# 12V--5V--3_3V.net
KiCad netlist of a schematic drawn in Altium Designer
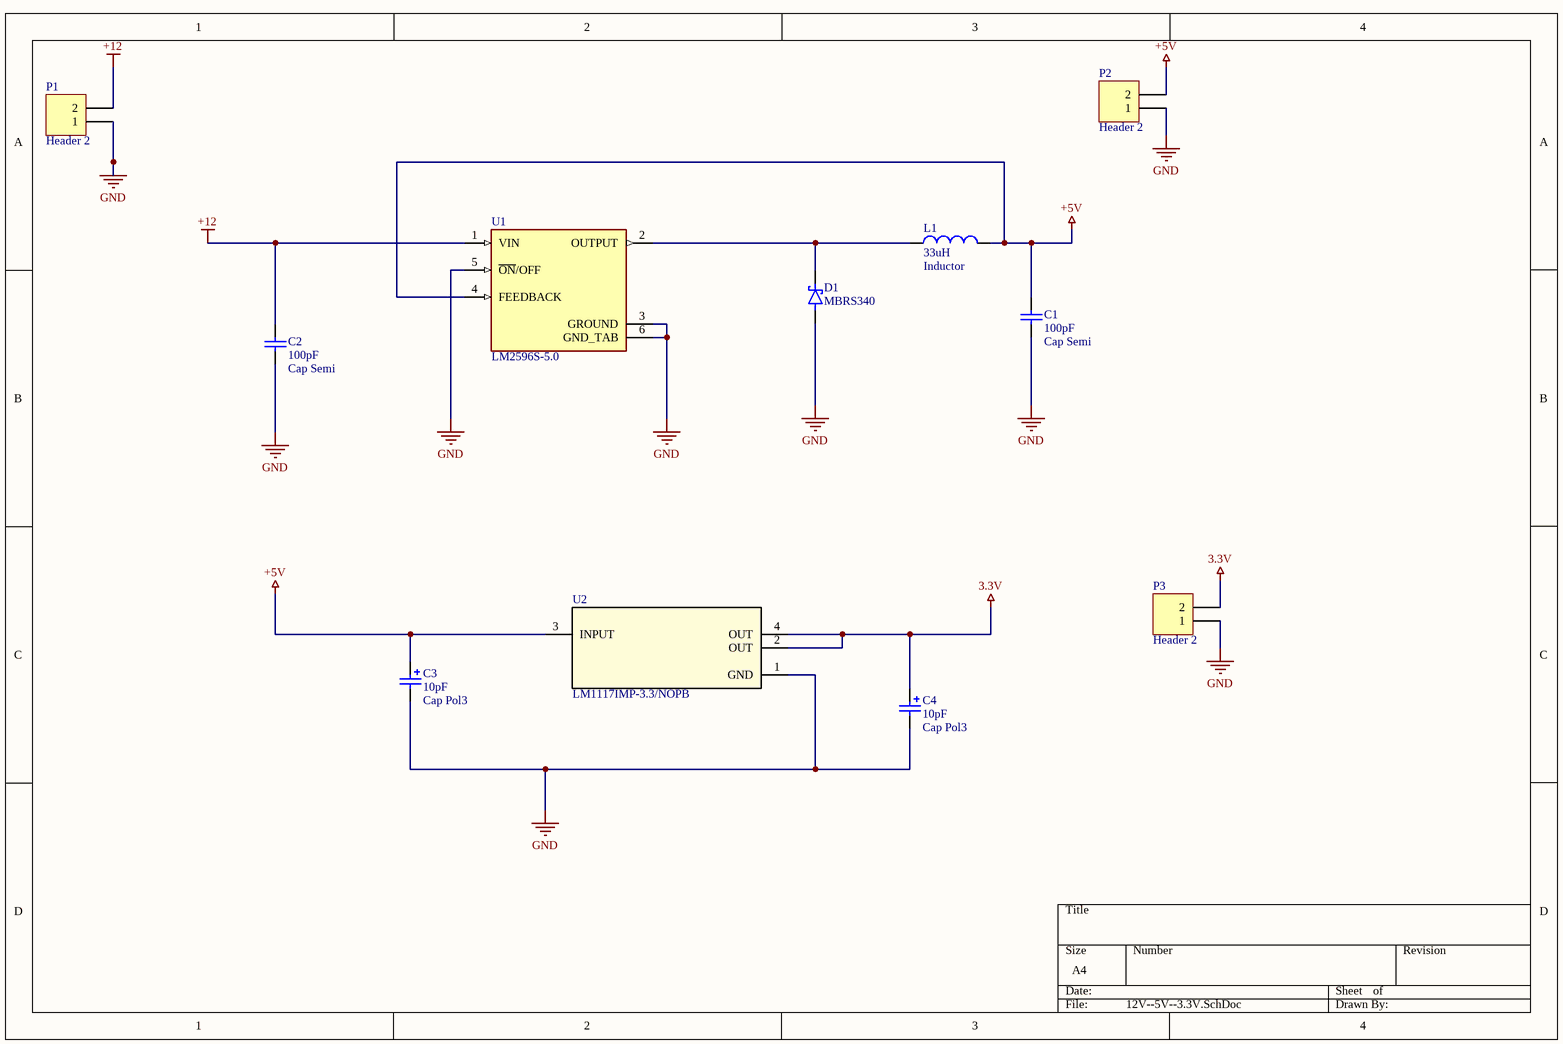
[diagram p0: 12V--5V--3.3V.SchDoc]

(export (version "E")
  (design (tool "Eeschema 10.0.6"))
  (components
    (comp (ref "C1")
      (value "Cap Semi")
      (footprint "C1206")
      (description "Capacitor (Semiconductor SIM Model)")
      (fields (field (name "ALTIUM_VALUE") "100pF") (field (name "PUBLISHER") "Altium Limited"))
      (libsource (lib "Miscellaneous Devices") (part "Cap Semi"))
    )
    (comp (ref "C2")
      (value "Cap Semi")
      (footprint "C1206")
      (description "Capacitor (Semiconductor SIM Model)")
      (fields (field (name "ALTIUM_VALUE") "100pF") (field (name "PUBLISHER") "Altium Limited"))
      (libsource (lib "Miscellaneous Devices") (part "Cap Semi"))
    )
    (comp (ref "C3")
      (value "Cap Pol3")
      (footprint "C0805")
      (description "Polarized Capacitor (Surface Mount)")
      (fields (field (name "ALTIUM_VALUE") "10pF") (field (name "PUBLISHER") "Altium Limited"))
      (libsource (lib "Miscellaneous Devices") (part "Cap Pol3"))
    )
    (comp (ref "C4")
      (value "Cap Pol3")
      (footprint "C0805")
      (description "Polarized Capacitor (Surface Mount)")
      (fields (field (name "ALTIUM_VALUE") "10pF") (field (name "PUBLISHER") "Altium Limited"))
      (libsource (lib "Miscellaneous Devices") (part "Cap Pol3"))
    )
    (comp (ref "D1")
      (value "MBRS340")
      (footprint "DIOM7959X261N")
      (description "Diode 40 V 4A Surface Mount DO-214AB (SMC)")
      (fields (field (name "MF") "onsemi"))
      (libsource (lib "MBRS340") (part "MBRS340"))
    )
    (comp (ref "L1")
      (value "Inductor")
      (footprint "0402-A")
      (fields (field (name "ALTIUM_VALUE") "33uH") (field (name "PUBLISHER") "Altium Limited"))
      (libsource (lib "Miscellaneous Devices") (part "Inductor"))
    )
    (comp (ref "P1")
      (value "Header 2")
      (footprint "HDR1X2")
      (description "Header, 2-Pin")
      (fields (field (name "PUBLISHER") "Altium Limited"))
      (libsource (lib "Miscellaneous Connectors") (part "Header 2"))
    )
    (comp (ref "P2")
      (value "Header 2")
      (footprint "HDR1X2")
      (description "Header, 2-Pin")
      (fields (field (name "PUBLISHER") "Altium Limited"))
      (libsource (lib "Miscellaneous Connectors") (part "Header 2"))
    )
    (comp (ref "P3")
      (value "Header 2")
      (footprint "HDR1X2")
      (description "Header, 2-Pin")
      (fields (field (name "PUBLISHER") "Altium Limited"))
      (libsource (lib "Miscellaneous Connectors") (part "Header 2"))
    )
    (comp (ref "U1")
      (value "LM2596S-5.0")
      (footprint "TO170P1524X483-6N")
      (description "SIMPLE SWITCHERÂ® 4.5V to 40V, 3A Low Component Count Step-Down Regulator")
      (fields (field (name "MF") "Texas Instruments") (field (name "MP") "LM2596S-5.0/NOPB"))
      (libsource (lib "LM2596S-5.0") (part "LM2596S-5.0"))
    )
    (comp (ref "U2")
      (value "LM1117IMP-3.3/NOPB")
      (footprint "DCY0004A_N")
      (description "800-mA 15-V linear voltage regulator 4-SOT-223 -40 to 125")
      (fields (field (name "COPYRIGHT") "Copyright (C) 2025 Ultra Librarian. All rights reserved."))
      (libsource (lib "LM1117IMP-3P3NOPB") (part "LM1117IMP-3.3NOPB"))
    )
  )
  (nets
    (net (code "1") (name "+5V") (class "Default")
      (node (ref "C1") (pin "2") (pinfunction "2_2") (pintype "passive"))
      (node (ref "C3") (pin "1") (pinfunction "1_1") (pintype "passive"))
      (node (ref "L1") (pin "2") (pinfunction "2_2") (pintype "passive"))
      (node (ref "P2") (pin "2") (pinfunction "2_2") (pintype "passive"))
      (node (ref "U1") (pin "4") (pinfunction "FEEDBACK_4") (pintype "input"))
      (node (ref "U2") (pin "3") (pinfunction "INPUT_3") (pintype "power_in"))
    )
    (net (code "2") (name "+12") (class "Default")
      (node (ref "C2") (pin "2") (pinfunction "2_2") (pintype "passive"))
      (node (ref "P1") (pin "2") (pinfunction "2_2") (pintype "passive"))
      (node (ref "U1") (pin "1") (pinfunction "VIN_1") (pintype "input"))
    )
    (net (code "3") (name "3.3V") (class "Default")
      (node (ref "C4") (pin "1") (pinfunction "1_1") (pintype "passive"))
      (node (ref "P3") (pin "2") (pinfunction "2_2") (pintype "passive"))
      (node (ref "U2") (pin "2") (pinfunction "OUT_2") (pintype "power_in"))
      (node (ref "U2") (pin "4") (pinfunction "OUT_4") (pintype "power_in"))
    )
    (net (code "4") (name "GND") (class "Default")
      (node (ref "C1") (pin "1") (pinfunction "1_1") (pintype "passive"))
      (node (ref "C2") (pin "1") (pinfunction "1_1") (pintype "passive"))
      (node (ref "C3") (pin "2") (pinfunction "2_2") (pintype "passive"))
      (node (ref "C4") (pin "2") (pinfunction "2_2") (pintype "passive"))
      (node (ref "D1") (pin "A") (pinfunction "A_A") (pintype "passive"))
      (node (ref "P1") (pin "1") (pinfunction "1_1") (pintype "passive"))
      (node (ref "P2") (pin "1") (pinfunction "1_1") (pintype "passive"))
      (node (ref "P3") (pin "1") (pinfunction "1_1") (pintype "passive"))
      (node (ref "U1") (pin "3") (pinfunction "GROUND_3") (pintype "power_in"))
      (node (ref "U1") (pin "5") (pinfunction "~{ON}/OFF_5") (pintype "input"))
      (node (ref "U1") (pin "6") (pinfunction "GND_TAB_6") (pintype "power_in"))
      (node (ref "U2") (pin "1") (pinfunction "GND_1") (pintype "power_in"))
    )
    (net (code "5") (name "Net-(D1-K)") (class "Default")
      (node (ref "D1") (pin "C") (pinfunction "K_C") (pintype "passive"))
      (node (ref "L1") (pin "1") (pinfunction "1_1") (pintype "passive"))
      (node (ref "U1") (pin "2") (pinfunction "OUTPUT_2") (pintype "output"))
    )
  )
)
